# SPI.net
KiCad netlist of a schematic drawn in Altium Designer
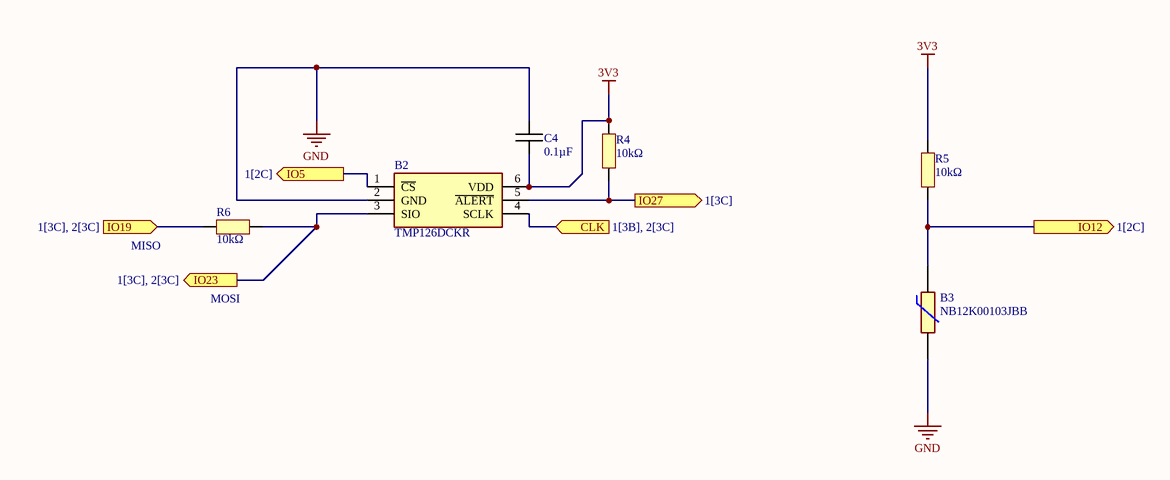
[diagram p0: SPI.SchDoc]

(export (version "E")
  (design (tool "Eeschema 10.0.6"))
  (components
    (comp (ref "B2")
      (value "TMP126DCKR")
      (footprint "SOT65P210X110-6N")
      (fields (field (name "MOUSER PART NUMBER") "595-TMP126DCKR"))
      (libsource (lib "SCHLibrary") (part "TMP126DCKR"))
    )
    (comp (ref "B3")
      (value "NB12K00103JBB")
      (footprint "RESC2212X50N")
      (description "NTC SMD Thermistor, NB12K, 10K, 5% AVX 10k 0805 Protection NTC Thermistor, 5s, 2 x 1.25 x 1.3mm")
      (fields (field (name "MOUSER PART NUMBER") "581-NB12K00103JBB"))
      (libsource (lib "SCHLibrary") (part "NB12K00103JBB"))
    )
    (comp (ref "C4")
      (value "0.1µF")
      (footprint "CAPC1005X06N")
      (libsource (lib "SCHLibrary") (part "Capacitor"))
    )
    (comp (ref "R4")
      (value "10kΩ")
      (footprint "RESC1005X06N")
      (libsource (lib "SCHLibrary") (part "Resistor"))
    )
    (comp (ref "R5") (value "10kΩ") (footprint "RESC1005X06N") (libsource (lib "") (part "Resistor_1")))
    (comp (ref "R6") (value "10kΩ") (footprint "RESC1005X06N") (libsource (lib "") (part "Resistor_2")))
  )
  (nets
    (net (code "1") (name "/CLK") (class "Default")
      (node (ref "B2") (pin "4") (pinfunction "SCLK_4") (pintype "passive"))
    )
    (net (code "2") (name "/IO5") (class "Default")
      (node (ref "B2") (pin "1") (pinfunction "~{CS}_1") (pintype "passive"))
    )
    (net (code "3") (name "/IO12") (class "Default")
      (node (ref "B3") (pin "1") (pinfunction "1_1") (pintype "passive"))
      (node (ref "R5") (pin "2") (pinfunction "2_2") (pintype "passive"))
    )
    (net (code "4") (name "/IO19") (class "Default")
      (node (ref "R6") (pin "2") (pinfunction "2_2") (pintype "passive"))
    )
    (net (code "5") (name "/IO23") (class "Default")
      (node (ref "B2") (pin "3") (pinfunction "SIO_3") (pintype "passive"))
      (node (ref "R6") (pin "1") (pinfunction "1_1") (pintype "passive"))
    )
    (net (code "6") (name "/IO27") (class "Default")
      (node (ref "B2") (pin "5") (pinfunction "~{ALERT}_5") (pintype "passive"))
      (node (ref "R4") (pin "1") (pinfunction "1_1") (pintype "passive"))
    )
    (net (code "7") (name "3V3") (class "Default")
      (node (ref "B2") (pin "6") (pinfunction "VDD_6") (pintype "passive"))
      (node (ref "C4") (pin "1") (pinfunction "1_1") (pintype "passive"))
      (node (ref "R4") (pin "2") (pinfunction "2_2") (pintype "passive"))
      (node (ref "R5") (pin "1") (pinfunction "1_1") (pintype "passive"))
    )
    (net (code "8") (name "GND") (class "Default")
      (node (ref "B2") (pin "2") (pinfunction "GND_2") (pintype "passive"))
      (node (ref "B3") (pin "2") (pinfunction "2_2") (pintype "passive"))
      (node (ref "C4") (pin "2") (pinfunction "2_2") (pintype "passive"))
    )
  )
)
